# RevB.net
KiCad netlist of a schematic drawn in EAGLE
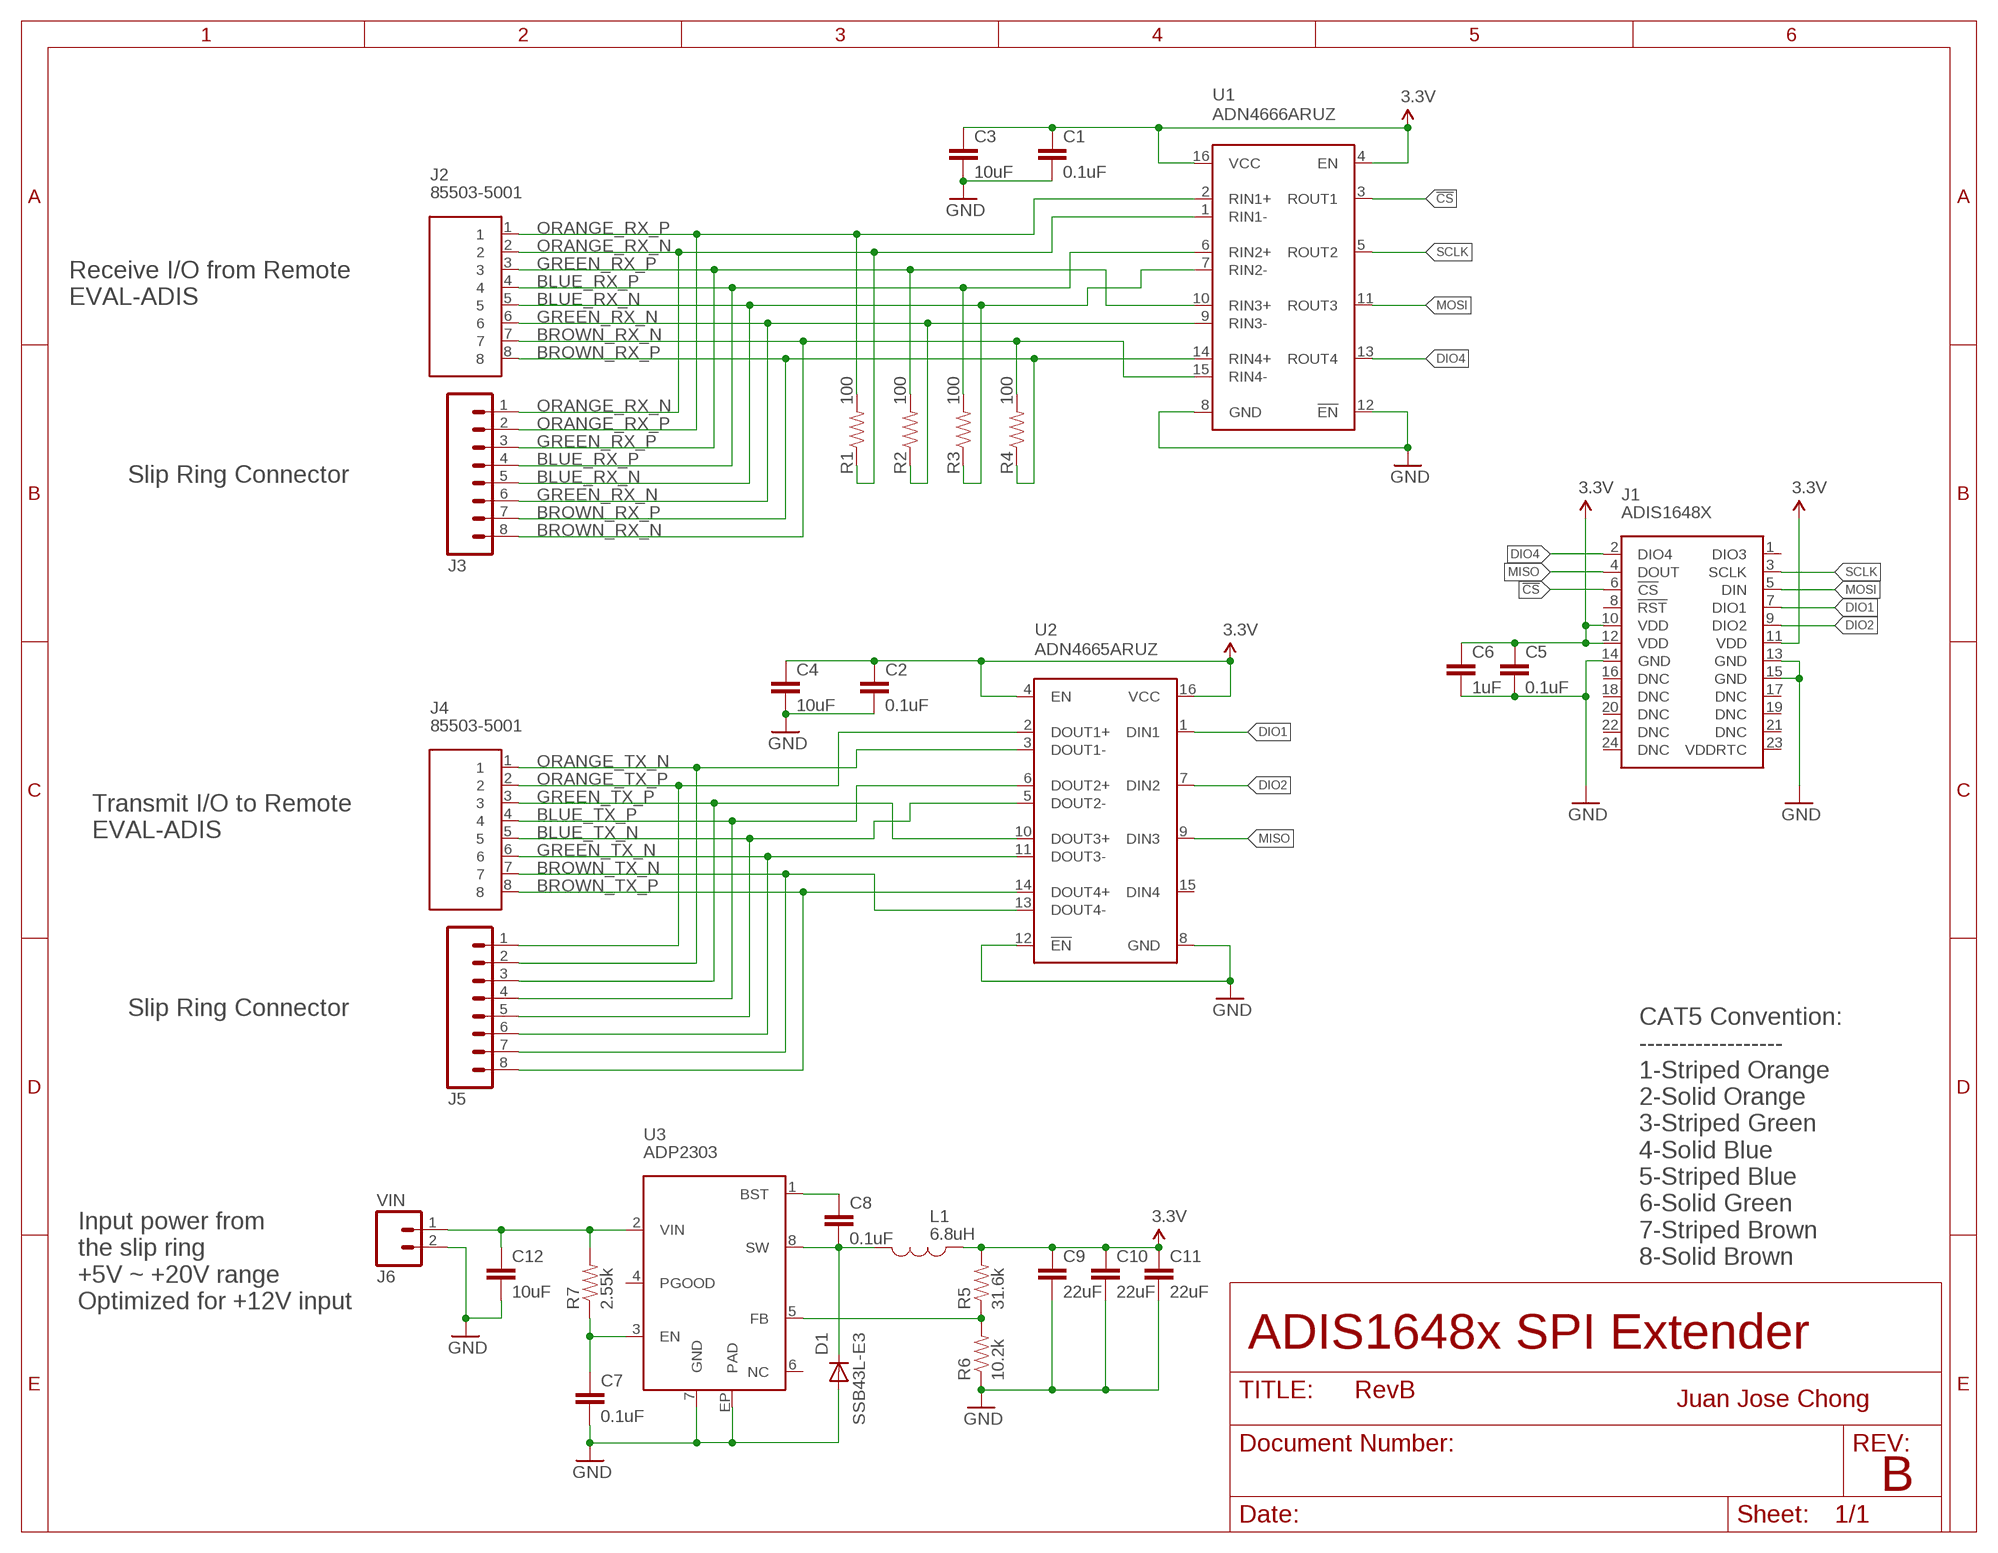
[diagram p0: schematic, sheet 1]

(export (version "E")
  (design (tool "Eeschema 10.0.6"))
  (components
    (comp (ref "C1")
      (value "0.1uF")
      (footprint "eagle-import:0603-CAP")
      (fields (field (name "PARTNO") "CL10B104KB8NNNC"))
      (libsource (lib "eagle-import") (part "CAP0603-CAP"))
    )
    (comp (ref "C2")
      (value "0.1uF")
      (footprint "eagle-import:0603-CAP")
      (fields (field (name "PARTNO") "CL10B104KB8NNNC"))
      (libsource (lib "eagle-import") (part "CAP0603-CAP"))
    )
    (comp (ref "C3")
      (value "10uF")
      (footprint "eagle-import:1206")
      (fields (field (name "PARTNO") "F931C106MAA"))
      (libsource (lib "eagle-import") (part "CAP1206"))
    )
    (comp (ref "C4")
      (value "10uF")
      (footprint "eagle-import:1206")
      (fields (field (name "PARTNO") "F931C106MAA"))
      (libsource (lib "eagle-import") (part "CAP1206"))
    )
    (comp (ref "C5")
      (value "0.1uF")
      (footprint "eagle-import:0603-CAP")
      (fields (field (name "PARTNO") "CL10B104KB8NNNC"))
      (libsource (lib "eagle-import") (part "CAP0603-CAP"))
    )
    (comp (ref "C6")
      (value "1uF")
      (footprint "eagle-import:0603-CAP")
      (fields (field (name "PARTNO") "GRM188R61C105KA93D"))
      (libsource (lib "eagle-import") (part "CAP0603-CAP"))
    )
    (comp (ref "C7")
      (value "0.1uF")
      (footprint "eagle-import:0603-CAP")
      (fields (field (name "PARTNO") "CL10B104KB8NNNC"))
      (libsource (lib "eagle-import") (part "CAP0603-CAP"))
    )
    (comp (ref "C8")
      (value "0.1uF")
      (footprint "eagle-import:0603-CAP")
      (fields (field (name "PARTNO") "CL10B104KB8NNNC"))
      (libsource (lib "eagle-import") (part "CAP0603-CAP"))
    )
    (comp (ref "C9")
      (value "22uF")
      (footprint "eagle-import:1210")
      (fields (field (name "PARTNO") "TLJA476M010R0600"))
      (libsource (lib "eagle-import") (part "CAP1210"))
    )
    (comp (ref "C10")
      (value "22uF")
      (footprint "eagle-import:1210")
      (fields (field (name "PARTNO") "TLJA476M010R0600"))
      (libsource (lib "eagle-import") (part "CAP1210"))
    )
    (comp (ref "C11")
      (value "22uF")
      (footprint "eagle-import:1210")
      (fields (field (name "PARTNO") "TLJA476M010R0600"))
      (libsource (lib "eagle-import") (part "CAP1210"))
    )
    (comp (ref "C12")
      (value "10uF")
      (footprint "eagle-import:1206")
      (fields (field (name "PARTNO") "TLJA476M010R0600"))
      (libsource (lib "eagle-import") (part "CAP1206"))
    )
    (comp (ref "D1")
      (value "SSB43L-E3")
      (footprint "eagle-import:DO214AA")
      (fields (field (name "PARTNO") "SSB43L-E3/52T"))
      (libsource (lib "eagle-import") (part "DIODE-DO214AA"))
    )
    (comp (ref "J1")
      (value "ADIS1648X")
      (footprint "eagle-import:ADIS1648X")
      (fields (field (name "PARTNO") "CLM-112-02-L-D"))
      (libsource (lib "eagle-import") (part "ADIS1648X"))
    )
    (comp (ref "J2")
      (value "85503-5001")
      (footprint "eagle-import:85503-5001")
      (fields (field (name "PARTNO") "855035001"))
      (libsource (lib "eagle-import") (part "85503-5001"))
    )
    (comp (ref "J3")
      (value "M08LOCK")
      (footprint "eagle-import:1X08_LOCK")
      (fields (field (name "PARTNO") "PREC008SAAN-RC"))
      (libsource (lib "eagle-import") (part "M08LOCK"))
    )
    (comp (ref "J4")
      (value "85503-5001")
      (footprint "eagle-import:85503-5001")
      (fields (field (name "PARTNO") "855035001"))
      (libsource (lib "eagle-import") (part "85503-5001"))
    )
    (comp (ref "J5")
      (value "M08LOCK")
      (footprint "eagle-import:1X08_LOCK")
      (fields (field (name "PARTNO") "PREC008SAAN-RC"))
      (libsource (lib "eagle-import") (part "M08LOCK"))
    )
    (comp (ref "J6")
      (value "VIN")
      (footprint "eagle-import:SCREWTERMINAL-3.5MM-2")
      (fields (field (name "PARTNO") "20020327-C021B01LF"))
      (libsource (lib "eagle-import") (part "M023.5MM"))
    )
    (comp (ref "L1")
      (value "6.8uH")
      (footprint "eagle-import:VLF10040")
      (fields (field (name "PARTNO") "VLF10040T-6R8N4R5"))
      (libsource (lib "eagle-import") (part "INDUCTOR"))
    )
    (comp (ref "R1")
      (value "100")
      (footprint "eagle-import:0603-RES")
      (fields (field (name "PARTNO") "ERJ-3EKF1000V"))
      (libsource (lib "eagle-import") (part "RESISTOR0603-RES"))
    )
    (comp (ref "R2")
      (value "100")
      (footprint "eagle-import:0603-RES")
      (fields (field (name "PARTNO") "ERJ-3EKF1000V"))
      (libsource (lib "eagle-import") (part "RESISTOR0603-RES"))
    )
    (comp (ref "R3")
      (value "100")
      (footprint "eagle-import:0603-RES")
      (fields (field (name "PARTNO") "ERJ-3EKF1000V"))
      (libsource (lib "eagle-import") (part "RESISTOR0603-RES"))
    )
    (comp (ref "R4")
      (value "100")
      (footprint "eagle-import:0603-RES")
      (fields (field (name "PARTNO") "ERJ-3EKF1000V"))
      (libsource (lib "eagle-import") (part "RESISTOR0603-RES"))
    )
    (comp (ref "R5")
      (value "31.6k")
      (footprint "eagle-import:0603-RES")
      (fields (field (name "PARTNO") "ERJ-3EKF3162V"))
      (libsource (lib "eagle-import") (part "RESISTOR0603-RES"))
    )
    (comp (ref "R6")
      (value "10.2k")
      (footprint "eagle-import:0603-RES")
      (fields (field (name "PARTNO") "ERJ-3EKF1022V"))
      (libsource (lib "eagle-import") (part "RESISTOR0603-RES"))
    )
    (comp (ref "R7")
      (value "2.55k")
      (footprint "eagle-import:0603-RES")
      (fields (field (name "PARTNO") "ERJ-3EKF2551V"))
      (libsource (lib "eagle-import") (part "RESISTOR0603-RES"))
    )
    (comp (ref "U1")
      (value "ADN4666ARUZ")
      (footprint "eagle-import:TSSOP-16")
      (libsource (lib "eagle-import") (part "ADN4666ARUZ"))
    )
    (comp (ref "U2")
      (value "ADN4665ARUZ")
      (footprint "eagle-import:TSSOP-16")
      (libsource (lib "eagle-import") (part "ADN4665ARUZ"))
    )
    (comp (ref "U3")
      (value "ADP2303")
      (footprint "eagle-import:SOIC-8-PAD")
      (fields (field (name "PARTNO") "ADP2303ARDZ"))
      (libsource (lib "eagle-import") (part "ADP2303"))
    )
  )
  (nets
    (net (code "1") (name "/BLUE_RX_N") (class "Default")
      (node (ref "J2") (pin "5") (pinfunction "5_5") (pintype "bidirectional"))
      (node (ref "J3") (pin "5") (pinfunction "5_5") (pintype "passive"))
      (node (ref "R3") (pin "1") (pinfunction "1_1") (pintype "passive"))
      (node (ref "U1") (pin "7") (pinfunction "RIN2-_7") (pintype "bidirectional"))
    )
    (net (code "2") (name "/BLUE_RX_P") (class "Default")
      (node (ref "J2") (pin "4") (pinfunction "4_4") (pintype "bidirectional"))
      (node (ref "J3") (pin "4") (pinfunction "4_4") (pintype "passive"))
      (node (ref "R3") (pin "2") (pinfunction "2_2") (pintype "passive"))
      (node (ref "U1") (pin "6") (pinfunction "RIN2+_6") (pintype "bidirectional"))
    )
    (net (code "3") (name "/BLUE_TX_N") (class "Default")
      (node (ref "J4") (pin "5") (pinfunction "5_5") (pintype "bidirectional"))
      (node (ref "J5") (pin "5") (pinfunction "5_5") (pintype "passive"))
      (node (ref "U2") (pin "5") (pinfunction "DOUT2-_5") (pintype "bidirectional"))
    )
    (net (code "4") (name "/BLUE_TX_P") (class "Default")
      (node (ref "J4") (pin "4") (pinfunction "4_4") (pintype "bidirectional"))
      (node (ref "J5") (pin "4") (pinfunction "4_4") (pintype "passive"))
      (node (ref "U2") (pin "6") (pinfunction "DOUT2+_6") (pintype "bidirectional"))
    )
    (net (code "5") (name "/BROWN_RX_N") (class "Default")
      (node (ref "J2") (pin "7") (pinfunction "7_7") (pintype "bidirectional"))
      (node (ref "J3") (pin "8") (pinfunction "8_8") (pintype "passive"))
      (node (ref "R4") (pin "2") (pinfunction "2_2") (pintype "passive"))
      (node (ref "U1") (pin "15") (pinfunction "RIN4-_15") (pintype "bidirectional"))
    )
    (net (code "6") (name "/BROWN_RX_P") (class "Default")
      (node (ref "J2") (pin "8") (pinfunction "8_8") (pintype "bidirectional"))
      (node (ref "J3") (pin "7") (pinfunction "7_7") (pintype "passive"))
      (node (ref "R4") (pin "1") (pinfunction "1_1") (pintype "passive"))
      (node (ref "U1") (pin "14") (pinfunction "RIN4+_14") (pintype "bidirectional"))
    )
    (net (code "7") (name "/BROWN_TX_N") (class "Default")
      (node (ref "J4") (pin "7") (pinfunction "7_7") (pintype "bidirectional"))
      (node (ref "J5") (pin "7") (pinfunction "7_7") (pintype "passive"))
      (node (ref "U2") (pin "13") (pinfunction "DOUT4-_13") (pintype "bidirectional"))
    )
    (net (code "8") (name "/BROWN_TX_P") (class "Default")
      (node (ref "J4") (pin "8") (pinfunction "8_8") (pintype "bidirectional"))
      (node (ref "J5") (pin "8") (pinfunction "8_8") (pintype "passive"))
      (node (ref "U2") (pin "14") (pinfunction "DOUT4+_14") (pintype "bidirectional"))
    )
    (net (code "9") (name "/GREEN_RX_N") (class "Default")
      (node (ref "J2") (pin "6") (pinfunction "6_6") (pintype "bidirectional"))
      (node (ref "J3") (pin "6") (pinfunction "6_6") (pintype "passive"))
      (node (ref "R2") (pin "1") (pinfunction "1_1") (pintype "passive"))
      (node (ref "U1") (pin "9") (pinfunction "RIN3-_9") (pintype "bidirectional"))
    )
    (net (code "10") (name "/GREEN_RX_P") (class "Default")
      (node (ref "J2") (pin "3") (pinfunction "3_3") (pintype "bidirectional"))
      (node (ref "J3") (pin "3") (pinfunction "3_3") (pintype "passive"))
      (node (ref "R2") (pin "2") (pinfunction "2_2") (pintype "passive"))
      (node (ref "U1") (pin "10") (pinfunction "RIN3+_10") (pintype "bidirectional"))
    )
    (net (code "11") (name "/GREEN_TX_N") (class "Default")
      (node (ref "J4") (pin "6") (pinfunction "6_6") (pintype "bidirectional"))
      (node (ref "J5") (pin "6") (pinfunction "6_6") (pintype "passive"))
      (node (ref "U2") (pin "11") (pinfunction "DOUT3-_11") (pintype "bidirectional"))
    )
    (net (code "12") (name "/GREEN_TX_P") (class "Default")
      (node (ref "J4") (pin "3") (pinfunction "3_3") (pintype "bidirectional"))
      (node (ref "J5") (pin "3") (pinfunction "3_3") (pintype "passive"))
      (node (ref "U2") (pin "10") (pinfunction "DOUT3+_10") (pintype "bidirectional"))
    )
    (net (code "13") (name "/ORANGE_RX_N") (class "Default")
      (node (ref "J2") (pin "2") (pinfunction "2_2") (pintype "bidirectional"))
      (node (ref "J3") (pin "1") (pinfunction "1_1") (pintype "passive"))
      (node (ref "R1") (pin "1") (pinfunction "1_1") (pintype "passive"))
      (node (ref "U1") (pin "1") (pinfunction "RIN1-_1") (pintype "bidirectional"))
    )
    (net (code "14") (name "/ORANGE_RX_P") (class "Default")
      (node (ref "J2") (pin "1") (pinfunction "1_1") (pintype "bidirectional"))
      (node (ref "J3") (pin "2") (pinfunction "2_2") (pintype "passive"))
      (node (ref "R1") (pin "2") (pinfunction "2_2") (pintype "passive"))
      (node (ref "U1") (pin "2") (pinfunction "RIN1+_2") (pintype "bidirectional"))
    )
    (net (code "15") (name "/ORANGE_TX_N") (class "Default")
      (node (ref "J4") (pin "1") (pinfunction "1_1") (pintype "bidirectional"))
      (node (ref "J5") (pin "2") (pinfunction "2_2") (pintype "passive"))
      (node (ref "U2") (pin "3") (pinfunction "DOUT1-_3") (pintype "bidirectional"))
    )
    (net (code "16") (name "/ORANGE_TX_P") (class "Default")
      (node (ref "J4") (pin "2") (pinfunction "2_2") (pintype "bidirectional"))
      (node (ref "J5") (pin "1") (pinfunction "1_1") (pintype "passive"))
      (node (ref "U2") (pin "2") (pinfunction "DOUT1+_2") (pintype "bidirectional"))
    )
    (net (code "17") (name "/~{CS}") (class "Default")
      (node (ref "J1") (pin "6") (pinfunction "~{CS}_6") (pintype "bidirectional"))
      (node (ref "U1") (pin "3") (pinfunction "ROUT1_3") (pintype "bidirectional"))
    )
    (net (code "18") (name "3.3V") (class "Default")
      (node (ref "C1") (pin "1") (pinfunction "1_1") (pintype "passive"))
      (node (ref "C10") (pin "1") (pinfunction "1_1") (pintype "passive"))
      (node (ref "C11") (pin "1") (pinfunction "1_1") (pintype "passive"))
      (node (ref "C2") (pin "1") (pinfunction "1_1") (pintype "passive"))
      (node (ref "C3") (pin "1") (pinfunction "1_1") (pintype "passive"))
      (node (ref "C4") (pin "1") (pinfunction "1_1") (pintype "passive"))
      (node (ref "C5") (pin "1") (pinfunction "1_1") (pintype "passive"))
      (node (ref "C6") (pin "1") (pinfunction "1_1") (pintype "passive"))
      (node (ref "C9") (pin "1") (pinfunction "1_1") (pintype "passive"))
      (node (ref "J1") (pin "10") (pinfunction "VDD_10") (pintype "bidirectional"))
      (node (ref "J1") (pin "11") (pinfunction "VDD_11") (pintype "bidirectional"))
      (node (ref "J1") (pin "12") (pinfunction "VDD_12") (pintype "bidirectional"))
      (node (ref "L1") (pin "P$1") (pinfunction "1_P$1") (pintype "passive"))
      (node (ref "R5") (pin "2") (pinfunction "2_2") (pintype "passive"))
      (node (ref "U1") (pin "16") (pinfunction "VCC_16") (pintype "bidirectional"))
      (node (ref "U1") (pin "4") (pinfunction "EN_4") (pintype "bidirectional"))
      (node (ref "U2") (pin "16") (pinfunction "VCC_16") (pintype "bidirectional"))
      (node (ref "U2") (pin "4") (pinfunction "EN_4") (pintype "bidirectional"))
    )
    (net (code "19") (name "DIO1") (class "Default")
      (node (ref "J1") (pin "7") (pinfunction "DIO1_7") (pintype "bidirectional"))
      (node (ref "U2") (pin "1") (pinfunction "DIN1_1") (pintype "bidirectional"))
    )
    (net (code "20") (name "DIO2") (class "Default")
      (node (ref "J1") (pin "9") (pinfunction "DIO2_9") (pintype "bidirectional"))
      (node (ref "U2") (pin "7") (pinfunction "DIN2_7") (pintype "bidirectional"))
    )
    (net (code "21") (name "DIO4") (class "Default")
      (node (ref "J1") (pin "2") (pinfunction "DIO4_2") (pintype "bidirectional"))
      (node (ref "U1") (pin "13") (pinfunction "ROUT4_13") (pintype "bidirectional"))
    )
    (net (code "22") (name "GND") (class "Default")
      (node (ref "C1") (pin "2") (pinfunction "2_2") (pintype "passive"))
      (node (ref "C10") (pin "2") (pinfunction "2_2") (pintype "passive"))
      (node (ref "C11") (pin "2") (pinfunction "2_2") (pintype "passive"))
      (node (ref "C12") (pin "2") (pinfunction "2_2") (pintype "passive"))
      (node (ref "C2") (pin "2") (pinfunction "2_2") (pintype "passive"))
      (node (ref "C3") (pin "2") (pinfunction "2_2") (pintype "passive"))
      (node (ref "C4") (pin "2") (pinfunction "2_2") (pintype "passive"))
      (node (ref "C5") (pin "2") (pinfunction "2_2") (pintype "passive"))
      (node (ref "C6") (pin "2") (pinfunction "2_2") (pintype "passive"))
      (node (ref "C7") (pin "2") (pinfunction "2_2") (pintype "passive"))
      (node (ref "C9") (pin "2") (pinfunction "2_2") (pintype "passive"))
      (node (ref "D1") (pin "A") (pinfunction "A_A") (pintype "passive"))
      (node (ref "J1") (pin "13") (pinfunction "GND_13") (pintype "bidirectional"))
      (node (ref "J1") (pin "14") (pinfunction "GND_14") (pintype "bidirectional"))
      (node (ref "J1") (pin "15") (pinfunction "GND_15") (pintype "bidirectional"))
      (node (ref "J6") (pin "2") (pinfunction "2_2") (pintype "passive"))
      (node (ref "R6") (pin "1") (pinfunction "1_1") (pintype "passive"))
      (node (ref "U1") (pin "12") (pinfunction "~{EN}_12") (pintype "bidirectional"))
      (node (ref "U1") (pin "8") (pinfunction "GND_8") (pintype "bidirectional"))
      (node (ref "U2") (pin "12") (pinfunction "~{EN}_12") (pintype "bidirectional"))
      (node (ref "U2") (pin "8") (pinfunction "GND_8") (pintype "bidirectional"))
      (node (ref "U3") (pin "7") (pinfunction "GND_7") (pintype "bidirectional"))
      (node (ref "U3") (pin "EP") (pinfunction "PAD_EP") (pintype "bidirectional"))
    )
    (net (code "23") (name "MISO") (class "Default")
      (node (ref "J1") (pin "4") (pinfunction "DOUT_4") (pintype "bidirectional"))
      (node (ref "U2") (pin "9") (pinfunction "DIN3_9") (pintype "bidirectional"))
    )
    (net (code "24") (name "MOSI") (class "Default")
      (node (ref "J1") (pin "5") (pinfunction "DIN_5") (pintype "bidirectional"))
      (node (ref "U1") (pin "11") (pinfunction "ROUT3_11") (pintype "bidirectional"))
    )
    (net (code "25") (name "Net-(L1-2)") (class "Default")
      (node (ref "C8") (pin "2") (pinfunction "2_2") (pintype "passive"))
      (node (ref "D1") (pin "C") (pinfunction "C_C") (pintype "passive"))
      (node (ref "L1") (pin "P$2") (pinfunction "2_P$2") (pintype "passive"))
      (node (ref "U3") (pin "8") (pinfunction "SW_8") (pintype "bidirectional"))
    )
    (net (code "26") (name "Net-(U3-BST)") (class "Default")
      (node (ref "C8") (pin "1") (pinfunction "1_1") (pintype "passive"))
      (node (ref "U3") (pin "1") (pinfunction "BST_1") (pintype "bidirectional"))
    )
    (net (code "27") (name "Net-(U3-EN)") (class "Default")
      (node (ref "C7") (pin "1") (pinfunction "1_1") (pintype "passive"))
      (node (ref "R7") (pin "1") (pinfunction "1_1") (pintype "passive"))
      (node (ref "U3") (pin "3") (pinfunction "EN_3") (pintype "bidirectional"))
    )
    (net (code "28") (name "Net-(U3-FB)") (class "Default")
      (node (ref "R5") (pin "1") (pinfunction "1_1") (pintype "passive"))
      (node (ref "R6") (pin "2") (pinfunction "2_2") (pintype "passive"))
      (node (ref "U3") (pin "5") (pinfunction "FB_5") (pintype "bidirectional"))
    )
    (net (code "29") (name "Net-(U3-VIN)") (class "Default")
      (node (ref "C12") (pin "1") (pinfunction "1_1") (pintype "passive"))
      (node (ref "J6") (pin "1") (pinfunction "1_1") (pintype "passive"))
      (node (ref "R7") (pin "2") (pinfunction "2_2") (pintype "passive"))
      (node (ref "U3") (pin "2") (pinfunction "VIN_2") (pintype "bidirectional"))
    )
    (net (code "30") (name "SCLK") (class "Default")
      (node (ref "J1") (pin "3") (pinfunction "SCLK_3") (pintype "bidirectional"))
      (node (ref "U1") (pin "5") (pinfunction "ROUT2_5") (pintype "bidirectional"))
    )
    (net (code "31") (name "unconnected-(J1-DIO3-Pad1)") (class "Default")
      (node (ref "J1") (pin "1") (pinfunction "DIO3_1") (pintype "bidirectional"))
    )
    (net (code "32") (name "unconnected-(J1-DNC-Pad16)") (class "Default")
      (node (ref "J1") (pin "16") (pinfunction "DNC_16") (pintype "bidirectional"))
    )
    (net (code "33") (name "unconnected-(J1-DNC-Pad17)") (class "Default")
      (node (ref "J1") (pin "17") (pinfunction "DNC_17") (pintype "bidirectional"))
    )
    (net (code "34") (name "unconnected-(J1-DNC-Pad18)") (class "Default")
      (node (ref "J1") (pin "18") (pinfunction "DNC_18") (pintype "bidirectional"))
    )
    (net (code "35") (name "unconnected-(J1-DNC-Pad19)") (class "Default")
      (node (ref "J1") (pin "19") (pinfunction "DNC_19") (pintype "bidirectional"))
    )
    (net (code "36") (name "unconnected-(J1-DNC-Pad20)") (class "Default")
      (node (ref "J1") (pin "20") (pinfunction "DNC_20") (pintype "bidirectional"))
    )
    (net (code "37") (name "unconnected-(J1-DNC-Pad21)") (class "Default")
      (node (ref "J1") (pin "21") (pinfunction "DNC_21") (pintype "bidirectional"))
    )
    (net (code "38") (name "unconnected-(J1-DNC-Pad22)") (class "Default")
      (node (ref "J1") (pin "22") (pinfunction "DNC_22") (pintype "bidirectional"))
    )
    (net (code "39") (name "unconnected-(J1-DNC-Pad24)") (class "Default")
      (node (ref "J1") (pin "24") (pinfunction "DNC_24") (pintype "bidirectional"))
    )
    (net (code "40") (name "unconnected-(J1-VDDRTC-Pad23)") (class "Default")
      (node (ref "J1") (pin "23") (pinfunction "VDDRTC_23") (pintype "bidirectional"))
    )
    (net (code "41") (name "unconnected-(J1-~{RST}-Pad8)") (class "Default")
      (node (ref "J1") (pin "8") (pinfunction "~{RST}_8") (pintype "bidirectional"))
    )
    (net (code "42") (name "unconnected-(U2-DIN4-Pad15)") (class "Default")
      (node (ref "U2") (pin "15") (pinfunction "DIN4_15") (pintype "bidirectional"))
    )
    (net (code "43") (name "unconnected-(U3-NC-Pad6)") (class "Default")
      (node (ref "U3") (pin "6") (pinfunction "NC_6") (pintype "bidirectional"))
    )
    (net (code "44") (name "unconnected-(U3-PGOOD-Pad4)") (class "Default")
      (node (ref "U3") (pin "4") (pinfunction "PGOOD_4") (pintype "bidirectional"))
    )
  )
)
